# cc2538-dev-v1.net
KiCad netlist of a schematic drawn in EAGLE
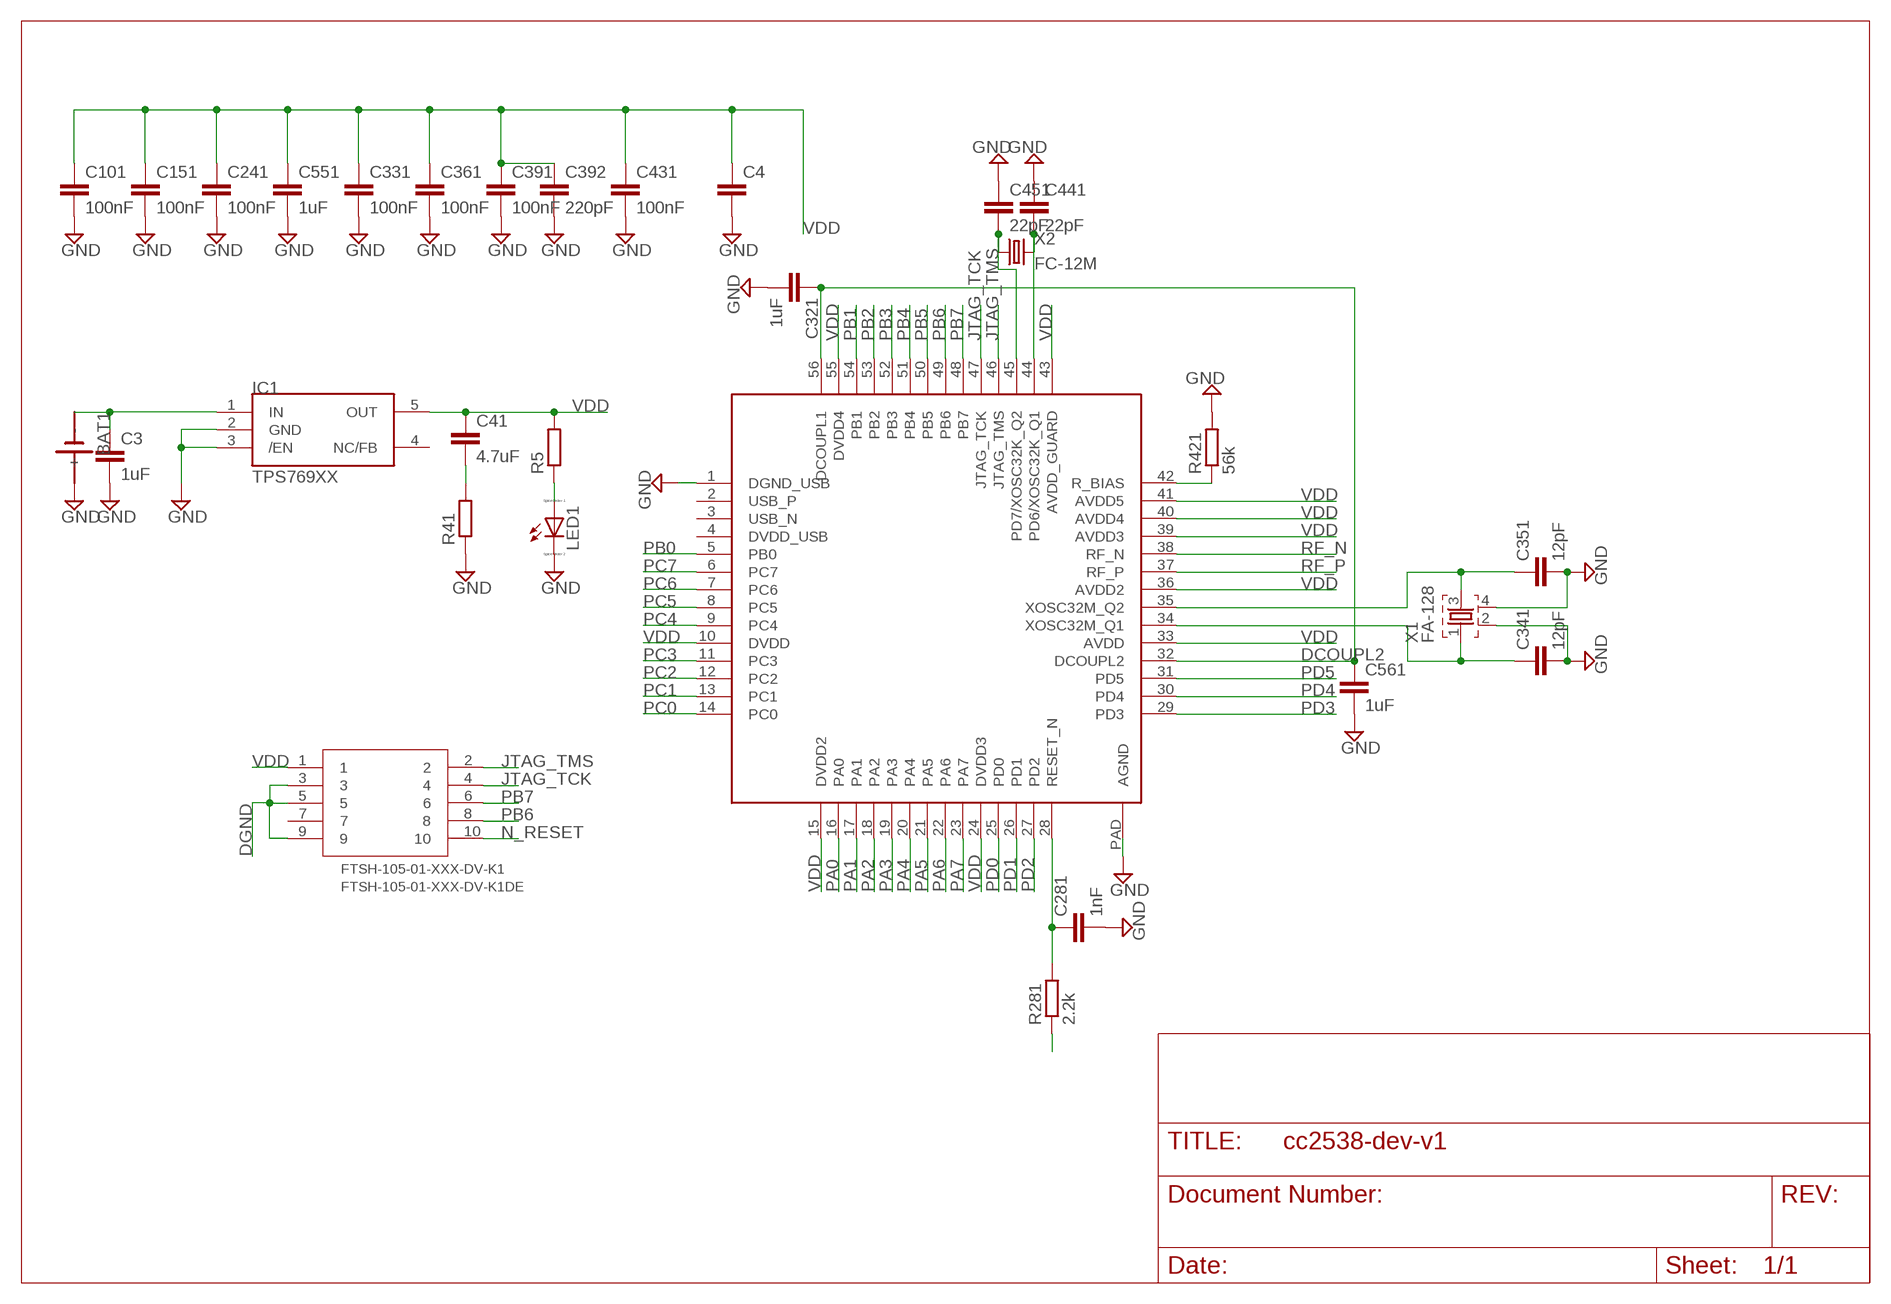
[diagram p0: schematic, sheet 1]

(export (version "E")
  (design (tool "Eeschema 10.0.6"))
  (components
    (comp (ref "BAT1")
      (value "SN2032")
      (footprint "eagle-import:SN2032")
      (libsource (lib "eagle-import") (part "SN2032"))
    )
    (comp (ref "C3")
      (value "1uF")
      (footprint "eagle-import:C0603")
      (libsource (lib "eagle-import") (part "C-EUC0603"))
    )
    (comp (ref "C4")
      (value "C-EUC0603")
      (footprint "eagle-import:C0603")
      (libsource (lib "eagle-import") (part "C-EUC0603"))
    )
    (comp (ref "C41")
      (value "4.7uF")
      (footprint "eagle-import:C0603")
      (libsource (lib "eagle-import") (part "C-EUC0603"))
    )
    (comp (ref "C101")
      (value "100nF")
      (footprint "eagle-import:C0402")
      (libsource (lib "eagle-import") (part "C-EUC0402"))
    )
    (comp (ref "C151")
      (value "100nF")
      (footprint "eagle-import:C0402")
      (libsource (lib "eagle-import") (part "C-EUC0402"))
    )
    (comp (ref "C241")
      (value "100nF")
      (footprint "eagle-import:C0402")
      (libsource (lib "eagle-import") (part "C-EUC0402"))
    )
    (comp (ref "C281")
      (value "1nF")
      (footprint "eagle-import:C0402")
      (libsource (lib "eagle-import") (part "C-EUC0402"))
    )
    (comp (ref "C321")
      (value "1uF")
      (footprint "eagle-import:C0402")
      (libsource (lib "eagle-import") (part "C-EUC0402"))
    )
    (comp (ref "C331")
      (value "100nF")
      (footprint "eagle-import:C0402")
      (libsource (lib "eagle-import") (part "C-EUC0402"))
    )
    (comp (ref "C341")
      (value "12pF")
      (footprint "eagle-import:C0402")
      (libsource (lib "eagle-import") (part "C-EUC0402"))
    )
    (comp (ref "C351")
      (value "12pF")
      (footprint "eagle-import:C0402")
      (libsource (lib "eagle-import") (part "C-EUC0402"))
    )
    (comp (ref "C361")
      (value "100nF")
      (footprint "eagle-import:C0402")
      (libsource (lib "eagle-import") (part "C-EUC0402"))
    )
    (comp (ref "C391")
      (value "100nF")
      (footprint "eagle-import:C0402")
      (libsource (lib "eagle-import") (part "C-EUC0402"))
    )
    (comp (ref "C392")
      (value "220pF")
      (footprint "eagle-import:C0402")
      (libsource (lib "eagle-import") (part "C-EUC0402"))
    )
    (comp (ref "C431")
      (value "100nF")
      (footprint "eagle-import:C0402")
      (libsource (lib "eagle-import") (part "C-EUC0402"))
    )
    (comp (ref "C441")
      (value "22pF")
      (footprint "eagle-import:C0402")
      (libsource (lib "eagle-import") (part "C-EUC0402"))
    )
    (comp (ref "C451")
      (value "22pF")
      (footprint "eagle-import:C0402")
      (libsource (lib "eagle-import") (part "C-EUC0402"))
    )
    (comp (ref "C551")
      (value "1uF")
      (footprint "eagle-import:C0402")
      (libsource (lib "eagle-import") (part "C-EUC0402"))
    )
    (comp (ref "C561")
      (value "1uF")
      (footprint "eagle-import:C0402")
      (libsource (lib "eagle-import") (part "C-EUC0402"))
    )
    (comp (ref "FTSH-105-01-XXX-DV-K1")
      (value "FTSH-105-01-XXX-DV-K1DE")
      (footprint "eagle-import:FTSH-105-01-XXX-DV-K")
      (libsource (lib "eagle-import") (part "FTSH-105-01-XXX-DV-KDE1"))
    )
    (comp (ref "IC1")
      (value "TPS769XX")
      (footprint "eagle-import:SOT23-5L")
      (libsource (lib "eagle-import") (part "TPS769XX"))
    )
    (comp (ref "LED1")
      (value "LED_ESML0603")
      (footprint "eagle-import:LED_SML0603")
      (libsource (lib "eagle-import") (part "LED_ESML0603"))
    )
    (comp (ref "R5")
      (value "R-EU_R0603")
      (footprint "eagle-import:R0603")
      (libsource (lib "eagle-import") (part "R-EU_R0603"))
    )
    (comp (ref "R41")
      (value "R-EU_R0603")
      (footprint "eagle-import:R0603")
      (libsource (lib "eagle-import") (part "R-EU_R0603"))
    )
    (comp (ref "R281")
      (value "2.2k")
      (footprint "eagle-import:R0402")
      (libsource (lib "eagle-import") (part "R-EU_R0402"))
    )
    (comp (ref "R421")
      (value "56k")
      (footprint "eagle-import:R0402")
      (libsource (lib "eagle-import") (part "R-EU_R0402"))
    )
    (comp (ref "U1")
      (value "CC2538")
      (footprint "eagle-import:QFN56")
      (libsource (lib "eagle-import") (part "CC2538"))
    )
    (comp (ref "X1")
      (value "FA-128")
      (footprint "eagle-import:FA-128")
      (libsource (lib "eagle-import") (part "FA-128"))
    )
    (comp (ref "X2")
      (value "FC-12M")
      (footprint "eagle-import:FC-12M")
      (libsource (lib "eagle-import") (part "FC-12M"))
    )
  )
  (nets
    (net (code "1") (name "/7") (class "Default")
      (node (ref "FTSH-105-01-XXX-DV-K1") (pin "7") (pinfunction "7_7") (pintype "power_in"))
    )
    (net (code "2") (name "/DCOUPL2") (class "Default")
      (node (ref "C321") (pin "1") (pinfunction "1_1") (pintype "passive"))
      (node (ref "C561") (pin "1") (pinfunction "1_1") (pintype "passive"))
      (node (ref "U1") (pin "32") (pinfunction "DCOUPL2_32") (pintype "bidirectional"))
      (node (ref "U1") (pin "56") (pinfunction "DCOUPL1_56") (pintype "bidirectional"))
    )
    (net (code "3") (name "/DGND") (class "Default")
      (node (ref "FTSH-105-01-XXX-DV-K1") (pin "3") (pinfunction "3_3") (pintype "power_in"))
      (node (ref "FTSH-105-01-XXX-DV-K1") (pin "5") (pinfunction "5_5") (pintype "power_in"))
      (node (ref "FTSH-105-01-XXX-DV-K1") (pin "9") (pinfunction "9_9") (pintype "power_in"))
    )
    (net (code "4") (name "/JTAG_TCK") (class "Default")
      (node (ref "FTSH-105-01-XXX-DV-K1") (pin "4") (pinfunction "4_4") (pintype "input"))
      (node (ref "U1") (pin "47") (pinfunction "JTAG_TCK_47") (pintype "bidirectional"))
    )
    (net (code "5") (name "/JTAG_TMS") (class "Default")
      (node (ref "FTSH-105-01-XXX-DV-K1") (pin "2") (pinfunction "2_2") (pintype "input"))
      (node (ref "U1") (pin "46") (pinfunction "JTAG_TMS_46") (pintype "bidirectional"))
    )
    (net (code "6") (name "/N_RESET") (class "Default")
      (node (ref "FTSH-105-01-XXX-DV-K1") (pin "10") (pinfunction "10_10") (pintype "input"))
    )
    (net (code "7") (name "/PA0") (class "Default")
      (node (ref "U1") (pin "16") (pinfunction "PA0_16") (pintype "bidirectional"))
    )
    (net (code "8") (name "/PA1") (class "Default")
      (node (ref "U1") (pin "17") (pinfunction "PA1_17") (pintype "bidirectional"))
    )
    (net (code "9") (name "/PA2") (class "Default")
      (node (ref "U1") (pin "18") (pinfunction "PA2_18") (pintype "bidirectional"))
    )
    (net (code "10") (name "/PA3") (class "Default")
      (node (ref "U1") (pin "19") (pinfunction "PA3_19") (pintype "bidirectional"))
    )
    (net (code "11") (name "/PA4") (class "Default")
      (node (ref "U1") (pin "20") (pinfunction "PA4_20") (pintype "bidirectional"))
    )
    (net (code "12") (name "/PA5") (class "Default")
      (node (ref "U1") (pin "21") (pinfunction "PA5_21") (pintype "bidirectional"))
    )
    (net (code "13") (name "/PA6") (class "Default")
      (node (ref "U1") (pin "22") (pinfunction "PA6_22") (pintype "bidirectional"))
    )
    (net (code "14") (name "/PA7") (class "Default")
      (node (ref "U1") (pin "23") (pinfunction "PA7_23") (pintype "bidirectional"))
    )
    (net (code "15") (name "/PB0") (class "Default")
      (node (ref "U1") (pin "5") (pinfunction "PB0_5") (pintype "bidirectional"))
    )
    (net (code "16") (name "/PB1") (class "Default")
      (node (ref "U1") (pin "54") (pinfunction "PB1_54") (pintype "bidirectional"))
    )
    (net (code "17") (name "/PB2") (class "Default")
      (node (ref "U1") (pin "53") (pinfunction "PB2_53") (pintype "bidirectional"))
    )
    (net (code "18") (name "/PB3") (class "Default")
      (node (ref "U1") (pin "52") (pinfunction "PB3_52") (pintype "bidirectional"))
    )
    (net (code "19") (name "/PB4") (class "Default")
      (node (ref "U1") (pin "51") (pinfunction "PB4_51") (pintype "bidirectional"))
    )
    (net (code "20") (name "/PB5") (class "Default")
      (node (ref "U1") (pin "50") (pinfunction "PB5_50") (pintype "bidirectional"))
    )
    (net (code "21") (name "/PB6") (class "Default")
      (node (ref "FTSH-105-01-XXX-DV-K1") (pin "8") (pinfunction "8_8") (pintype "input"))
      (node (ref "U1") (pin "49") (pinfunction "PB6_49") (pintype "bidirectional"))
    )
    (net (code "22") (name "/PB7") (class "Default")
      (node (ref "FTSH-105-01-XXX-DV-K1") (pin "6") (pinfunction "6_6") (pintype "input"))
      (node (ref "U1") (pin "48") (pinfunction "PB7_48") (pintype "bidirectional"))
    )
    (net (code "23") (name "/PC0") (class "Default")
      (node (ref "U1") (pin "14") (pinfunction "PC0_14") (pintype "bidirectional"))
    )
    (net (code "24") (name "/PC1") (class "Default")
      (node (ref "U1") (pin "13") (pinfunction "PC1_13") (pintype "bidirectional"))
    )
    (net (code "25") (name "/PC2") (class "Default")
      (node (ref "U1") (pin "12") (pinfunction "PC2_12") (pintype "bidirectional"))
    )
    (net (code "26") (name "/PC3") (class "Default")
      (node (ref "U1") (pin "11") (pinfunction "PC3_11") (pintype "bidirectional"))
    )
    (net (code "27") (name "/PC4") (class "Default")
      (node (ref "U1") (pin "9") (pinfunction "PC4_9") (pintype "bidirectional"))
    )
    (net (code "28") (name "/PC5") (class "Default")
      (node (ref "U1") (pin "8") (pinfunction "PC5_8") (pintype "bidirectional"))
    )
    (net (code "29") (name "/PC6") (class "Default")
      (node (ref "U1") (pin "7") (pinfunction "PC6_7") (pintype "bidirectional"))
    )
    (net (code "30") (name "/PC7") (class "Default")
      (node (ref "U1") (pin "6") (pinfunction "PC7_6") (pintype "bidirectional"))
    )
    (net (code "31") (name "/PD0") (class "Default")
      (node (ref "U1") (pin "25") (pinfunction "PD0_25") (pintype "bidirectional"))
    )
    (net (code "32") (name "/PD1") (class "Default")
      (node (ref "U1") (pin "26") (pinfunction "PD1_26") (pintype "bidirectional"))
    )
    (net (code "33") (name "/PD2") (class "Default")
      (node (ref "U1") (pin "27") (pinfunction "PD2_27") (pintype "bidirectional"))
    )
    (net (code "34") (name "/PD3") (class "Default")
      (node (ref "U1") (pin "29") (pinfunction "PD3_29") (pintype "bidirectional"))
    )
    (net (code "35") (name "/PD4") (class "Default")
      (node (ref "U1") (pin "30") (pinfunction "PD4_30") (pintype "bidirectional"))
    )
    (net (code "36") (name "/PD5") (class "Default")
      (node (ref "U1") (pin "31") (pinfunction "PD5_31") (pintype "bidirectional"))
    )
    (net (code "37") (name "/RF_N") (class "Default")
      (node (ref "U1") (pin "38") (pinfunction "RF_N_38") (pintype "bidirectional"))
    )
    (net (code "38") (name "/RF_P") (class "Default")
      (node (ref "U1") (pin "37") (pinfunction "RF_P_37") (pintype "bidirectional"))
    )
    (net (code "39") (name "/VDD") (class "Default")
      (node (ref "C101") (pin "1") (pinfunction "1_1") (pintype "passive"))
      (node (ref "C151") (pin "1") (pinfunction "1_1") (pintype "passive"))
      (node (ref "C241") (pin "1") (pinfunction "1_1") (pintype "passive"))
      (node (ref "C331") (pin "1") (pinfunction "1_1") (pintype "passive"))
      (node (ref "C361") (pin "1") (pinfunction "1_1") (pintype "passive"))
      (node (ref "C391") (pin "1") (pinfunction "1_1") (pintype "passive"))
      (node (ref "C392") (pin "1") (pinfunction "1_1") (pintype "passive"))
      (node (ref "C4") (pin "1") (pinfunction "1_1") (pintype "passive"))
      (node (ref "C41") (pin "1") (pinfunction "1_1") (pintype "passive"))
      (node (ref "C431") (pin "1") (pinfunction "1_1") (pintype "passive"))
      (node (ref "C551") (pin "1") (pinfunction "1_1") (pintype "passive"))
      (node (ref "FTSH-105-01-XXX-DV-K1") (pin "1") (pinfunction "1_1") (pintype "power_in"))
      (node (ref "IC1") (pin "5") (pinfunction "OUT_5") (pintype "power_in"))
      (node (ref "R5") (pin "2") (pinfunction "2_2") (pintype "passive"))
      (node (ref "U1") (pin "10") (pinfunction "DVDD_10") (pintype "bidirectional"))
      (node (ref "U1") (pin "15") (pinfunction "DVDD2_15") (pintype "bidirectional"))
      (node (ref "U1") (pin "24") (pinfunction "DVDD3_24") (pintype "bidirectional"))
      (node (ref "U1") (pin "33") (pinfunction "AVDD_33") (pintype "bidirectional"))
      (node (ref "U1") (pin "36") (pinfunction "AVDD2_36") (pintype "bidirectional"))
      (node (ref "U1") (pin "39") (pinfunction "AVDD3_39") (pintype "bidirectional"))
      (node (ref "U1") (pin "40") (pinfunction "AVDD4_40") (pintype "bidirectional"))
      (node (ref "U1") (pin "41") (pinfunction "AVDD5_41") (pintype "bidirectional"))
      (node (ref "U1") (pin "43") (pinfunction "AVDD_GUARD_43") (pintype "bidirectional"))
      (node (ref "U1") (pin "55") (pinfunction "DVDD4_55") (pintype "bidirectional"))
    )
    (net (code "40") (name "GND") (class "Default")
      (node (ref "BAT1") (pin "+") (pinfunction "+_+") (pintype "passive"))
      (node (ref "C101") (pin "2") (pinfunction "2_2") (pintype "passive"))
      (node (ref "C151") (pin "2") (pinfunction "2_2") (pintype "passive"))
      (node (ref "C241") (pin "2") (pinfunction "2_2") (pintype "passive"))
      (node (ref "C281") (pin "2") (pinfunction "2_2") (pintype "passive"))
      (node (ref "C3") (pin "2") (pinfunction "2_2") (pintype "passive"))
      (node (ref "C321") (pin "2") (pinfunction "2_2") (pintype "passive"))
      (node (ref "C331") (pin "2") (pinfunction "2_2") (pintype "passive"))
      (node (ref "C341") (pin "2") (pinfunction "2_2") (pintype "passive"))
      (node (ref "C351") (pin "2") (pinfunction "2_2") (pintype "passive"))
      (node (ref "C361") (pin "2") (pinfunction "2_2") (pintype "passive"))
      (node (ref "C391") (pin "2") (pinfunction "2_2") (pintype "passive"))
      (node (ref "C392") (pin "2") (pinfunction "2_2") (pintype "passive"))
      (node (ref "C4") (pin "2") (pinfunction "2_2") (pintype "passive"))
      (node (ref "C431") (pin "2") (pinfunction "2_2") (pintype "passive"))
      (node (ref "C441") (pin "1") (pinfunction "1_1") (pintype "passive"))
      (node (ref "C451") (pin "1") (pinfunction "1_1") (pintype "passive"))
      (node (ref "C551") (pin "2") (pinfunction "2_2") (pintype "passive"))
      (node (ref "C561") (pin "2") (pinfunction "2_2") (pintype "passive"))
      (node (ref "IC1") (pin "2") (pinfunction "GND_2") (pintype "power_in"))
      (node (ref "IC1") (pin "3") (pinfunction "/EN_3") (pintype "passive"))
      (node (ref "LED1") (pin "C") (pinfunction "C_C") (pintype "passive"))
      (node (ref "R41") (pin "1") (pinfunction "1_1") (pintype "passive"))
      (node (ref "R421") (pin "2") (pinfunction "2_2") (pintype "passive"))
      (node (ref "U1") (pin "1") (pinfunction "DGND_USB_1") (pintype "bidirectional"))
      (node (ref "U1") (pin "PAD") (pinfunction "AGND_PAD") (pintype "bidirectional"))
      (node (ref "X1") (pin "2") (pinfunction "2_2") (pintype "passive"))
      (node (ref "X1") (pin "4") (pinfunction "4_4") (pintype "passive"))
    )
    (net (code "41") (name "Net-(C41-Pad2)") (class "Default")
      (node (ref "C41") (pin "2") (pinfunction "2_2") (pintype "passive"))
      (node (ref "R41") (pin "2") (pinfunction "2_2") (pintype "passive"))
    )
    (net (code "42") (name "Net-(IC1-IN)") (class "Default")
      (node (ref "BAT1") (pin "-") (pinfunction "-_-") (pintype "passive"))
      (node (ref "C3") (pin "1") (pinfunction "1_1") (pintype "passive"))
      (node (ref "IC1") (pin "1") (pinfunction "IN_1") (pintype "power_in"))
    )
    (net (code "43") (name "Net-(LED1-PadA)") (class "Default")
      (node (ref "LED1") (pin "A") (pinfunction "A_A") (pintype "passive"))
      (node (ref "R5") (pin "1") (pinfunction "1_1") (pintype "passive"))
    )
    (net (code "44") (name "Net-(U1-PD6{slash}XOSC32K_Q1)") (class "Default")
      (node (ref "C441") (pin "2") (pinfunction "2_2") (pintype "passive"))
      (node (ref "U1") (pin "44") (pinfunction "PD6/XOSC32K_Q1_44") (pintype "bidirectional"))
      (node (ref "X2") (pin "2") (pinfunction "2_2") (pintype "passive"))
    )
    (net (code "45") (name "Net-(U1-PD7{slash}XOSC32K_Q2)") (class "Default")
      (node (ref "C451") (pin "2") (pinfunction "2_2") (pintype "passive"))
      (node (ref "U1") (pin "45") (pinfunction "PD7/XOSC32K_Q2_45") (pintype "bidirectional"))
      (node (ref "X2") (pin "1") (pinfunction "1_1") (pintype "passive"))
    )
    (net (code "46") (name "Net-(U1-RESET_N)") (class "Default")
      (node (ref "C281") (pin "1") (pinfunction "1_1") (pintype "passive"))
      (node (ref "R281") (pin "2") (pinfunction "2_2") (pintype "passive"))
      (node (ref "U1") (pin "28") (pinfunction "RESET_N_28") (pintype "bidirectional"))
    )
    (net (code "47") (name "Net-(U1-R_BIAS)") (class "Default")
      (node (ref "R421") (pin "1") (pinfunction "1_1") (pintype "passive"))
      (node (ref "U1") (pin "42") (pinfunction "R_BIAS_42") (pintype "bidirectional"))
    )
    (net (code "48") (name "Net-(U1-XOSC32M_Q1)") (class "Default")
      (node (ref "C341") (pin "1") (pinfunction "1_1") (pintype "passive"))
      (node (ref "U1") (pin "34") (pinfunction "XOSC32M_Q1_34") (pintype "bidirectional"))
      (node (ref "X1") (pin "1") (pinfunction "1_1") (pintype "passive"))
    )
    (net (code "49") (name "Net-(U1-XOSC32M_Q2)") (class "Default")
      (node (ref "C351") (pin "1") (pinfunction "1_1") (pintype "passive"))
      (node (ref "U1") (pin "35") (pinfunction "XOSC32M_Q2_35") (pintype "bidirectional"))
      (node (ref "X1") (pin "3") (pinfunction "3_3") (pintype "passive"))
    )
    (net (code "50") (name "unconnected-(IC1-NC{slash}FB-Pad4)") (class "Default")
      (node (ref "IC1") (pin "4") (pinfunction "NC/FB_4") (pintype "passive"))
    )
    (net (code "51") (name "unconnected-(R281-Pad1)") (class "Default")
      (node (ref "R281") (pin "1") (pinfunction "1_1") (pintype "passive"))
    )
    (net (code "52") (name "unconnected-(U1-DVDD_USB-Pad4)") (class "Default")
      (node (ref "U1") (pin "4") (pinfunction "DVDD_USB_4") (pintype "bidirectional"))
    )
    (net (code "53") (name "unconnected-(U1-USB_N-Pad3)") (class "Default")
      (node (ref "U1") (pin "3") (pinfunction "USB_N_3") (pintype "bidirectional"))
    )
    (net (code "54") (name "unconnected-(U1-USB_P-Pad2)") (class "Default")
      (node (ref "U1") (pin "2") (pinfunction "USB_P_2") (pintype "bidirectional"))
    )
  )
)
